# Batt_Charger.net
KiCad netlist of a schematic drawn in Altium Designer
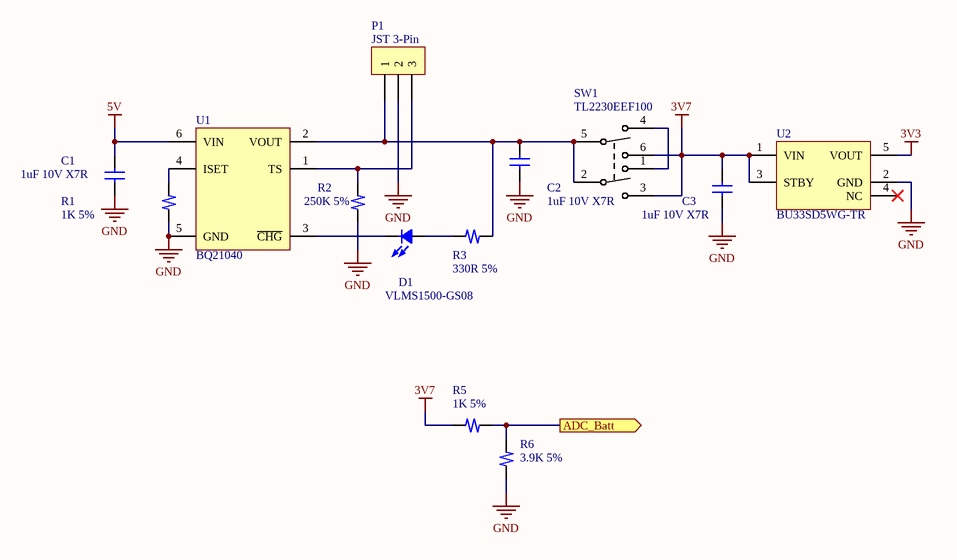
[diagram p0: Batt_Charger.SchDoc]

(export (version "E")
  (design (tool "Eeschema 10.0.6"))
  (components
    (comp (ref "C1")
      (value "1uF 10V X7R")
      (footprint "C_0402")
      (description "Ceramic Capacitor SMD 0402")
      (libsource (lib "Oxy_Lib") (part "Ceramic Capacitor"))
    )
    (comp (ref "C2")
      (value "1uF 10V X7R")
      (footprint "C_0402")
      (description "Ceramic Capacitor SMD 0402")
      (libsource (lib "Oxy_Lib") (part "Ceramic Capacitor"))
    )
    (comp (ref "C3")
      (value "1uF 10V X7R")
      (footprint "C_0402")
      (description "Ceramic Capacitor SMD 0402")
      (libsource (lib "Oxy_Lib") (part "Ceramic Capacitor"))
    )
    (comp (ref "D1")
      (value "VLMS1500-GS08")
      (footprint "L_0402")
      (description "LED Diode SMD 0402")
      (libsource (lib "Oxy_Lib") (part "Diode LED"))
    )
    (comp (ref "P1")
      (value "JST 3-Pin")
      (footprint "BATT CONNECTOR")
      (description "JST Right Angle Connector THD 3-Pin PN: PRT-09750")
      (libsource (lib "Oxy_Lib") (part "3-Pin Header"))
    )
    (comp (ref "R1")
      (value "1K 5%")
      (footprint "R_0402")
      (description "Resistor SMD 0402")
      (libsource (lib "Oxy_Lib") (part "Resistor"))
    )
    (comp (ref "R2")
      (value "250K 5%")
      (footprint "R_0402")
      (description "Resistor SMD 0402")
      (libsource (lib "Oxy_Lib") (part "Resistor"))
    )
    (comp (ref "R3")
      (value "330R 5%")
      (footprint "R_0402")
      (description "Resistor SMD 0402")
      (libsource (lib "") (part "Resistor_1"))
    )
    (comp (ref "R5")
      (value "1K 5%")
      (footprint "R_0402")
      (description "Resistor SMD 0402")
      (libsource (lib "Oxy_Lib") (part "Resistor"))
    )
    (comp (ref "R6")
      (value "3.9K 5%")
      (footprint "R_0402")
      (description "Resistor SMD 0402")
      (libsource (lib "Oxy_Lib") (part "Resistor"))
    )
    (comp (ref "SW1")
      (value "TL2230EEF100")
      (footprint "TL2230")
      (description "PushButton Switch Latching THD TL2230EEF100")
      (libsource (lib "Oxy_Lib") (part "PushButton Switch"))
    )
    (comp (ref "U1")
      (value "BQ21040")
      (footprint "SOT-23 (6)")
      (description "BQ21040 0.8A Sigle Cell Li-Ion Battery Charger SOT-23")
      (libsource (lib "Oxy_Lib") (part "BQ21040 Charger"))
    )
    (comp (ref "U2")
      (value "BU33SD5WG-TR")
      (footprint "SSOP5")
      (description "LDO Voltage Regulator 1ch 500mA CMOS SSOP5")
      (libsource (lib "Oxy_Lib") (part "LDO CMOS Regulator"))
    )
  )
  (nets
    (net (code "1") (name "/ADC_Batt") (class "Default")
      (node (ref "R5") (pin "2") (pinfunction "2_2") (pintype "passive"))
      (node (ref "R6") (pin "2") (pinfunction "2_2") (pintype "passive"))
    )
    (net (code "2") (name "3V3") (class "Default")
      (node (ref "U2") (pin "5") (pinfunction "VOUT_5") (pintype "passive"))
    )
    (net (code "3") (name "3V7") (class "Default")
      (node (ref "C3") (pin "1") (pinfunction "1_1") (pintype "passive"))
      (node (ref "R5") (pin "1") (pinfunction "1_1") (pintype "passive"))
      (node (ref "SW1") (pin "3") (pinfunction "3_3") (pintype "passive"))
      (node (ref "SW1") (pin "6") (pinfunction "6_6") (pintype "passive"))
      (node (ref "U2") (pin "1") (pinfunction "VIN_1") (pintype "passive"))
      (node (ref "U2") (pin "3") (pinfunction "STBY_3") (pintype "passive"))
    )
    (net (code "4") (name "5V") (class "Default")
      (node (ref "C1") (pin "1") (pinfunction "1_1") (pintype "passive"))
      (node (ref "U1") (pin "6") (pinfunction "VIN_6") (pintype "passive"))
    )
    (net (code "5") (name "GND") (class "Default")
      (node (ref "C1") (pin "2") (pinfunction "2_2") (pintype "passive"))
      (node (ref "C2") (pin "2") (pinfunction "2_2") (pintype "passive"))
      (node (ref "C3") (pin "2") (pinfunction "2_2") (pintype "passive"))
      (node (ref "P1") (pin "2") (pinfunction "2_2") (pintype "passive"))
      (node (ref "R1") (pin "1") (pinfunction "1_1") (pintype "passive"))
      (node (ref "R2") (pin "1") (pinfunction "1_1") (pintype "passive"))
      (node (ref "R6") (pin "1") (pinfunction "1_1") (pintype "passive"))
      (node (ref "U1") (pin "5") (pinfunction "GND_5") (pintype "passive"))
      (node (ref "U2") (pin "2") (pinfunction "GND_2") (pintype "passive"))
    )
    (net (code "6") (name "Net-(D1-Pad1)") (class "Default")
      (node (ref "D1") (pin "1") (pinfunction "1_1") (pintype "passive"))
      (node (ref "R3") (pin "2") (pinfunction "2_2") (pintype "passive"))
    )
    (net (code "7") (name "Net-(SW1-Pad1)") (class "Default")
      (node (ref "SW1") (pin "1") (pinfunction "1_1") (pintype "passive"))
      (node (ref "SW1") (pin "4") (pinfunction "4_4") (pintype "passive"))
    )
    (net (code "8") (name "Net-(U1-ISET)") (class "Default")
      (node (ref "R1") (pin "2") (pinfunction "2_2") (pintype "passive"))
      (node (ref "U1") (pin "4") (pinfunction "ISET_4") (pintype "passive"))
    )
    (net (code "9") (name "Net-(U1-TS)") (class "Default")
      (node (ref "P1") (pin "3") (pinfunction "3_3") (pintype "passive"))
      (node (ref "R2") (pin "2") (pinfunction "2_2") (pintype "passive"))
      (node (ref "U1") (pin "1") (pinfunction "TS_1") (pintype "passive"))
    )
    (net (code "10") (name "Net-(U1-VOUT)") (class "Default")
      (node (ref "C2") (pin "1") (pinfunction "1_1") (pintype "passive"))
      (node (ref "P1") (pin "1") (pinfunction "1_1") (pintype "passive"))
      (node (ref "R3") (pin "1") (pinfunction "1_1") (pintype "passive"))
      (node (ref "SW1") (pin "2") (pinfunction "2_2") (pintype "passive"))
      (node (ref "SW1") (pin "5") (pinfunction "5_5") (pintype "passive"))
      (node (ref "U1") (pin "2") (pinfunction "VOUT_2") (pintype "passive"))
    )
    (net (code "11") (name "Net-(U1-~{CHG})") (class "Default")
      (node (ref "D1") (pin "2") (pinfunction "2_2") (pintype "passive"))
      (node (ref "U1") (pin "3") (pinfunction "~{CHG}_3") (pintype "passive"))
    )
    (net (code "12") (name "unconnected-(U2-NC-Pad4)") (class "Default")
      (node (ref "U2") (pin "4") (pinfunction "NC_4") (pintype "passive+no_connect"))
    )
  )
)
